# main.net
KiCad netlist of a schematic drawn in EAGLE
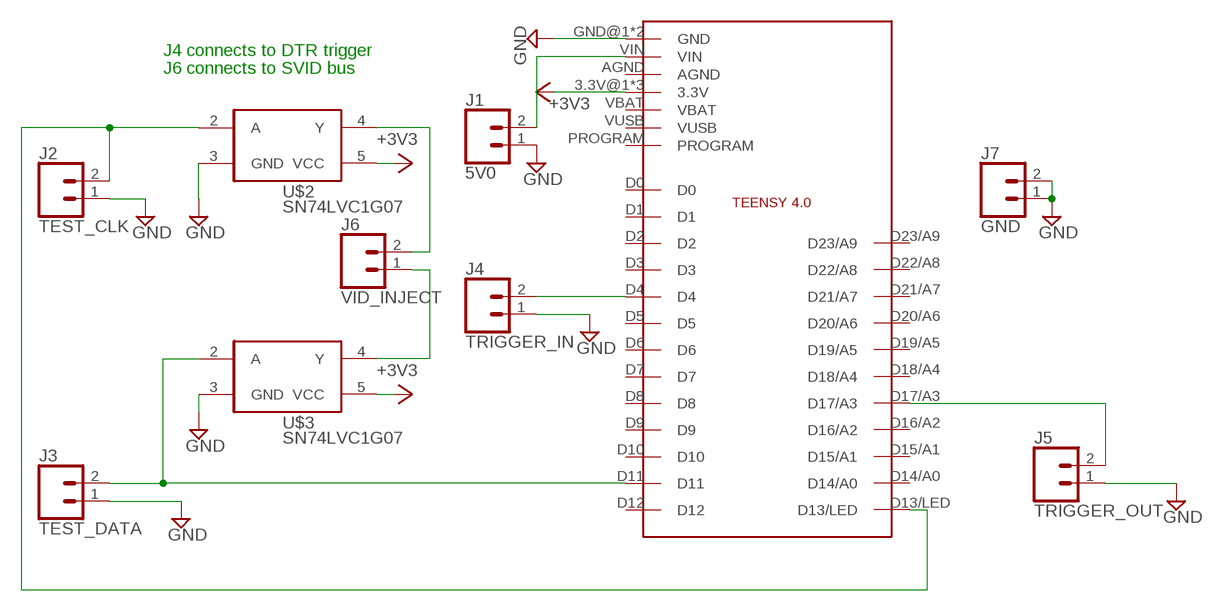
[diagram p0: schematic, sheet 1]

(export (version "E")
  (design (tool "Eeschema 10.0.6"))
  (components
    (comp (ref "J1")
      (value "5V0")
      (footprint "eagle-import:1X02")
      (libsource (lib "eagle-import") (part "CONN_02"))
    )
    (comp (ref "J2")
      (value "TEST_CLK")
      (footprint "eagle-import:1X02")
      (libsource (lib "eagle-import") (part "CONN_02"))
    )
    (comp (ref "J3")
      (value "TEST_DATA")
      (footprint "eagle-import:1X02")
      (libsource (lib "eagle-import") (part "CONN_02"))
    )
    (comp (ref "J4")
      (value "TRIGGER_IN")
      (footprint "eagle-import:1X02")
      (libsource (lib "eagle-import") (part "CONN_02"))
    )
    (comp (ref "J5")
      (value "TRIGGER_OUT")
      (footprint "eagle-import:1X02")
      (libsource (lib "eagle-import") (part "CONN_02"))
    )
    (comp (ref "J6")
      (value "VID_INJECT")
      (footprint "eagle-import:1X02")
      (libsource (lib "eagle-import") (part "CONN_02"))
    )
    (comp (ref "J7")
      (value "GND")
      (footprint "eagle-import:1X02")
      (libsource (lib "eagle-import") (part "CONN_02"))
    )
    (comp (ref "U$1")
      (value "TEENSY4.0")
      (footprint "eagle-import:TEENSY4.0")
      (libsource (lib "eagle-import") (part "TEENSY4.0"))
    )
    (comp (ref "U$2")
      (value "SN74LVC1G07")
      (footprint "eagle-import:SOT353-1")
      (libsource (lib "eagle-import") (part "SN74LVC1G07"))
    )
    (comp (ref "U$3")
      (value "SN74LVC1G07")
      (footprint "eagle-import:SOT353-1")
      (libsource (lib "eagle-import") (part "SN74LVC1G07"))
    )
  )
  (nets
    (net (code "1") (name "+3V3") (class "Default")
      (node (ref "U$1") (pin "3.3V@1") (pinfunction "3.3V_3.3V@1") (pintype "bidirectional"))
      (node (ref "U$1") (pin "3.3V@2") (pinfunction "3.3V_3.3V@2") (pintype "bidirectional"))
      (node (ref "U$1") (pin "ON/OFF") (pinfunction "3.3V_ON/OFF") (pintype "bidirectional"))
      (node (ref "U$2") (pin "5") (pinfunction "VCC_5") (pintype "power_in"))
      (node (ref "U$3") (pin "5") (pinfunction "VCC_5") (pintype "power_in"))
    )
    (net (code "2") (name "GND") (class "Default")
      (node (ref "J1") (pin "1") (pinfunction "1_1") (pintype "passive"))
      (node (ref "J2") (pin "1") (pinfunction "1_1") (pintype "passive"))
      (node (ref "J3") (pin "1") (pinfunction "1_1") (pintype "passive"))
      (node (ref "J4") (pin "1") (pinfunction "1_1") (pintype "passive"))
      (node (ref "J5") (pin "1") (pinfunction "1_1") (pintype "passive"))
      (node (ref "J7") (pin "1") (pinfunction "1_1") (pintype "passive"))
      (node (ref "J7") (pin "2") (pinfunction "2_2") (pintype "passive"))
      (node (ref "U$1") (pin "GND@1") (pinfunction "GND_GND@1") (pintype "bidirectional"))
      (node (ref "U$1") (pin "GND@2") (pinfunction "GND_GND@2") (pintype "bidirectional"))
      (node (ref "U$2") (pin "3") (pinfunction "GND_3") (pintype "power_in"))
      (node (ref "U$3") (pin "3") (pinfunction "GND_3") (pintype "power_in"))
    )
    (net (code "3") (name "Net-(J1-Pad2)") (class "Default")
      (node (ref "J1") (pin "2") (pinfunction "2_2") (pintype "passive"))
      (node (ref "U$1") (pin "VIN") (pinfunction "VIN_VIN") (pintype "bidirectional"))
    )
    (net (code "4") (name "Net-(J4-Pad2)") (class "Default")
      (node (ref "J4") (pin "2") (pinfunction "2_2") (pintype "passive"))
      (node (ref "U$1") (pin "D4") (pinfunction "D4_D4") (pintype "bidirectional"))
    )
    (net (code "5") (name "Net-(J5-Pad2)") (class "Default")
      (node (ref "J5") (pin "2") (pinfunction "2_2") (pintype "passive"))
      (node (ref "U$1") (pin "D17/A3") (pinfunction "D17/A3_D17/A3") (pintype "bidirectional"))
    )
    (net (code "6") (name "Net-(U$2-A)") (class "Default")
      (node (ref "J2") (pin "2") (pinfunction "2_2") (pintype "passive"))
      (node (ref "U$1") (pin "D13/LED") (pinfunction "D13/LED_D13/LED") (pintype "bidirectional"))
      (node (ref "U$2") (pin "2") (pinfunction "A_2") (pintype "input"))
    )
    (net (code "7") (name "Net-(U$2-Y)") (class "Default")
      (node (ref "J6") (pin "2") (pinfunction "2_2") (pintype "passive"))
      (node (ref "U$2") (pin "4") (pinfunction "Y_4") (pintype "output"))
    )
    (net (code "8") (name "Net-(U$3-A)") (class "Default")
      (node (ref "J3") (pin "2") (pinfunction "2_2") (pintype "passive"))
      (node (ref "U$1") (pin "D11") (pinfunction "D11_D11") (pintype "bidirectional"))
      (node (ref "U$3") (pin "2") (pinfunction "A_2") (pintype "input"))
    )
    (net (code "9") (name "Net-(U$3-Y)") (class "Default")
      (node (ref "J6") (pin "1") (pinfunction "1_1") (pintype "passive"))
      (node (ref "U$3") (pin "4") (pinfunction "Y_4") (pintype "output"))
    )
    (net (code "10") (name "unconnected-(U$1-PadAGND)") (class "Default")
      (node (ref "U$1") (pin "AGND") (pinfunction "AGND_AGND") (pintype "bidirectional"))
    )
    (net (code "11") (name "unconnected-(U$1-PadD0)") (class "Default")
      (node (ref "U$1") (pin "D0") (pinfunction "D0_D0") (pintype "bidirectional"))
    )
    (net (code "12") (name "unconnected-(U$1-PadD1)") (class "Default")
      (node (ref "U$1") (pin "D1") (pinfunction "D1_D1") (pintype "bidirectional"))
    )
    (net (code "13") (name "unconnected-(U$1-PadD2)") (class "Default")
      (node (ref "U$1") (pin "D2") (pinfunction "D2_D2") (pintype "bidirectional"))
    )
    (net (code "14") (name "unconnected-(U$1-PadD3)") (class "Default")
      (node (ref "U$1") (pin "D3") (pinfunction "D3_D3") (pintype "bidirectional"))
    )
    (net (code "15") (name "unconnected-(U$1-PadD5)") (class "Default")
      (node (ref "U$1") (pin "D5") (pinfunction "D5_D5") (pintype "bidirectional"))
    )
    (net (code "16") (name "unconnected-(U$1-PadD6)") (class "Default")
      (node (ref "U$1") (pin "D6") (pinfunction "D6_D6") (pintype "bidirectional"))
    )
    (net (code "17") (name "unconnected-(U$1-PadD7)") (class "Default")
      (node (ref "U$1") (pin "D7") (pinfunction "D7_D7") (pintype "bidirectional"))
    )
    (net (code "18") (name "unconnected-(U$1-PadD8)") (class "Default")
      (node (ref "U$1") (pin "D8") (pinfunction "D8_D8") (pintype "bidirectional"))
    )
    (net (code "19") (name "unconnected-(U$1-PadD9)") (class "Default")
      (node (ref "U$1") (pin "D9") (pinfunction "D9_D9") (pintype "bidirectional"))
    )
    (net (code "20") (name "unconnected-(U$1-PadD10)") (class "Default")
      (node (ref "U$1") (pin "D10") (pinfunction "D10_D10") (pintype "bidirectional"))
    )
    (net (code "21") (name "unconnected-(U$1-PadD12)") (class "Default")
      (node (ref "U$1") (pin "D12") (pinfunction "D12_D12") (pintype "bidirectional"))
    )
    (net (code "22") (name "unconnected-(U$1-PadD14{slash}A0)") (class "Default")
      (node (ref "U$1") (pin "D14/A0") (pinfunction "D14/A0_D14/A0") (pintype "bidirectional"))
    )
    (net (code "23") (name "unconnected-(U$1-PadD15{slash}A1)") (class "Default")
      (node (ref "U$1") (pin "D15/A1") (pinfunction "D15/A1_D15/A1") (pintype "bidirectional"))
    )
    (net (code "24") (name "unconnected-(U$1-PadD16{slash}A2)") (class "Default")
      (node (ref "U$1") (pin "D16/A2") (pinfunction "D16/A2_D16/A2") (pintype "bidirectional"))
    )
    (net (code "25") (name "unconnected-(U$1-PadD18{slash}A4)") (class "Default")
      (node (ref "U$1") (pin "D18/A4") (pinfunction "D18/A4_D18/A4") (pintype "bidirectional"))
    )
    (net (code "26") (name "unconnected-(U$1-PadD19{slash}A5)") (class "Default")
      (node (ref "U$1") (pin "D19/A5") (pinfunction "D19/A5_D19/A5") (pintype "bidirectional"))
    )
    (net (code "27") (name "unconnected-(U$1-PadD20{slash}A6)") (class "Default")
      (node (ref "U$1") (pin "D20/A6") (pinfunction "D20/A6_D20/A6") (pintype "bidirectional"))
    )
    (net (code "28") (name "unconnected-(U$1-PadD21{slash}A7)") (class "Default")
      (node (ref "U$1") (pin "D21/A7") (pinfunction "D21/A7_D21/A7") (pintype "bidirectional"))
    )
    (net (code "29") (name "unconnected-(U$1-PadD22{slash}A8)") (class "Default")
      (node (ref "U$1") (pin "D22/A8") (pinfunction "D22/A8_D22/A8") (pintype "bidirectional"))
    )
    (net (code "30") (name "unconnected-(U$1-PadD23{slash}A9)") (class "Default")
      (node (ref "U$1") (pin "D23/A9") (pinfunction "D23/A9_D23/A9") (pintype "bidirectional"))
    )
    (net (code "31") (name "unconnected-(U$1-PadPROGRAM)") (class "Default")
      (node (ref "U$1") (pin "PROGRAM") (pinfunction "PROGRAM_PROGRAM") (pintype "bidirectional"))
    )
    (net (code "32") (name "unconnected-(U$1-PadVBAT)") (class "Default")
      (node (ref "U$1") (pin "VBAT") (pinfunction "VBAT_VBAT") (pintype "bidirectional"))
    )
    (net (code "33") (name "unconnected-(U$1-PadVUSB)") (class "Default")
      (node (ref "U$1") (pin "VUSB") (pinfunction "VUSB_VUSB") (pintype "bidirectional"))
    )
  )
)
